# design.net
KiCad netlist of a schematic drawn in Altium Designer
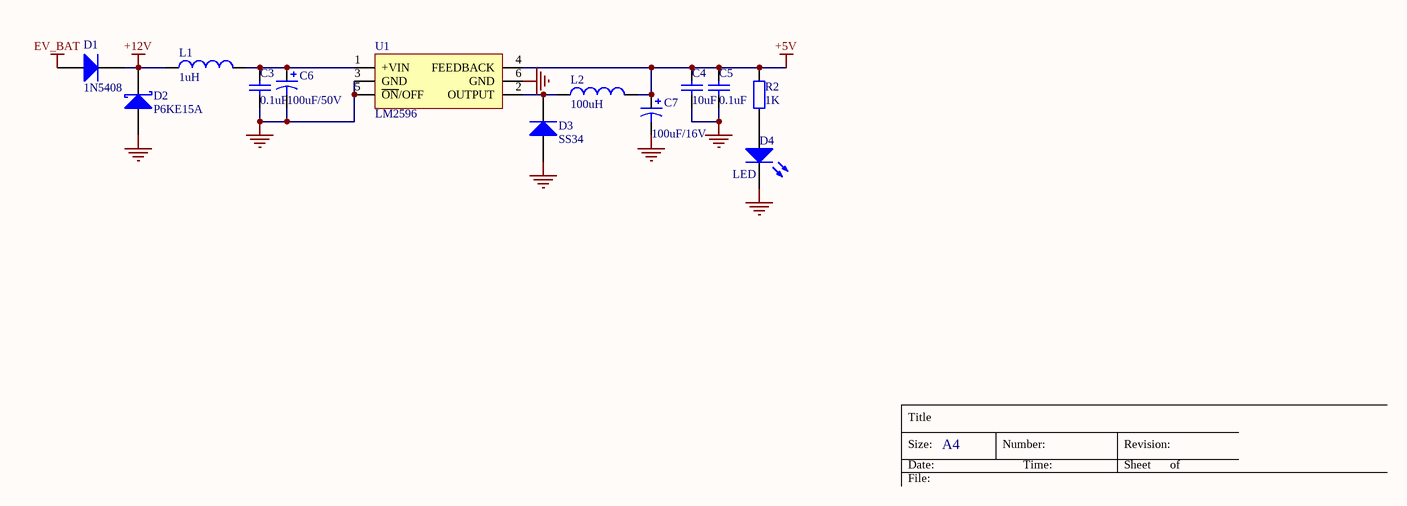
[diagram p0: 电源模块.SchDoc]

(export (version "E")
  (design (tool "Eeschema 10.0.6"))
  (components
    (comp (ref "C3")
      (value "0.1uF")
      (footprint "0603-L")
      (description "Ceramic, X7R, 100V, 10%, 0603")
      (fields (field (name "Comment") "Cap") (field (name "PUBLISHER") "Altium Limited"))
      (libsource (lib "Resistor") (part "CC0603KRX7R0BB104"))
    )
    (comp (ref "C4")
      (value "10uF")
      (footprint "0603-L")
      (description "Capacitor")
      (fields (field (name "Comment") "Cap") (field (name "PUBLISHER") "Altium Limited"))
      (libsource (lib "Miscellaneous Devices") (part "Cap"))
    )
    (comp (ref "C5")
      (value "0.1uF")
      (footprint "0603-L")
      (description "Ceramic, X7R, 100V, 10%, 0603")
      (fields (field (name "Comment") "Cap") (field (name "PUBLISHER") "Altium Limited"))
      (libsource (lib "Resistor") (part "CC0603KRX7R0BB104"))
    )
    (comp (ref "C6")
      (value "100uF/50V")
      (footprint "CAP220uF,16V,6.3*7.7mm")
      (description "Polarized Capacitor (Radial)")
      (fields (field (name "Comment") "Cap Pol1") (field (name "PUBLISHER") "Altium Limited"))
      (libsource (lib "Miscellaneous Devices") (part "Cap Pol1"))
    )
    (comp (ref "C7")
      (value "100uF/16V")
      (footprint "CAP220uF,16V,6.3*7.7mm")
      (description "Polarized Capacitor (Radial)")
      (fields (field (name "Comment") "Cap Pol1") (field (name "PUBLISHER") "Altium Limited"))
      (libsource (lib "Miscellaneous Devices") (part "Cap Pol1"))
    )
    (comp (ref "D1")
      (value "1N5408")
      (footprint "DO-201AD")
      (description "3 Amp Medium Power Silicon Rectifier Diode")
      (fields (field (name "PUBLISHER") "Altium Limited"))
      (libsource (lib "Miscellaneous Devices") (part "Diode 1N5408"))
    )
    (comp (ref "D2")
      (value "P6KE15A")
      (footprint "P6KE15A")
      (description "Schottky Diode")
      (fields (field (name "PUBLISHER") "Altium Limited"))
      (libsource (lib "Miscellaneous Devices") (part "D Schottky"))
    )
    (comp (ref "D3")
      (value "SS34")
      (footprint "SMC")
      (description "3 Amp Medium Power Silicon Rectifier Diode")
      (fields (field (name "PUBLISHER") "Altium Limited"))
      (libsource (lib "Miscellaneous Devices") (part "Diode 1N5408"))
    )
    (comp (ref "D4")
      (value "LED")
      (footprint "0603-L")
      (description "Typical INFRARED GaAs LED")
      (fields (field (name "PUBLISHER") "Altium Limited"))
      (libsource (lib "Miscellaneous Devices") (part "LED0"))
    )
    (comp (ref "L1")
      (value "1uH")
      (footprint "0603-L")
      (description "Inductor")
      (fields (field (name "PUBLISHER") "Altium Limited"))
      (libsource (lib "Miscellaneous Devices") (part "Inductor"))
    )
    (comp (ref "L2")
      (value "100uH")
      (footprint "IND-10*10*5")
      (description "Inductor")
      (fields (field (name "PUBLISHER") "Altium Limited"))
      (libsource (lib "Miscellaneous Devices") (part "Inductor"))
    )
    (comp (ref "R2")
      (value "1K")
      (footprint "0603-L")
      (description "Resistor")
      (fields (field (name "Comment") "Res2") (field (name "PUBLISHER") "Altium Limited"))
      (libsource (lib "Miscellaneous Devices") (part "Res2"))
    )
    (comp (ref "U1") (value "LM2596") (footprint "TO263, LM2576") (libsource (lib "BMS") (part "LM2576")))
  )
  (nets
    (net (code "1") (name "+5V") (class "Default")
      (node (ref "C4") (pin "2") (pinfunction "2_2") (pintype "passive"))
      (node (ref "C5") (pin "2") (pinfunction "2_2") (pintype "passive"))
      (node (ref "C7") (pin "1") (pinfunction "1_1") (pintype "passive"))
      (node (ref "L2") (pin "2") (pinfunction "2_2") (pintype "passive"))
      (node (ref "R2") (pin "1") (pinfunction "1_1") (pintype "passive"))
      (node (ref "U1") (pin "4") (pinfunction "FEEDBACK_4") (pintype "power_in"))
    )
    (net (code "2") (name "+12V") (class "Default")
      (node (ref "D1") (pin "2") (pinfunction "K_2") (pintype "passive"))
      (node (ref "D2") (pin "2") (pinfunction "K_2") (pintype "passive"))
      (node (ref "L1") (pin "1") (pinfunction "1_1") (pintype "passive"))
    )
    (net (code "3") (name "EV_BAT") (class "Default")
      (node (ref "D1") (pin "1") (pinfunction "A_1") (pintype "passive"))
    )
    (net (code "4") (name "GND") (class "Default")
      (node (ref "C3") (pin "1") (pinfunction "1_1") (pintype "passive"))
      (node (ref "C4") (pin "1") (pinfunction "1_1") (pintype "passive"))
      (node (ref "C5") (pin "1") (pinfunction "1_1") (pintype "passive"))
      (node (ref "C6") (pin "2") (pinfunction "2_2") (pintype "passive"))
      (node (ref "C7") (pin "2") (pinfunction "2_2") (pintype "passive"))
      (node (ref "D2") (pin "1") (pinfunction "A_1") (pintype "passive"))
      (node (ref "D3") (pin "1") (pinfunction "A_1") (pintype "passive"))
      (node (ref "D4") (pin "2") (pinfunction "K_2") (pintype "passive"))
      (node (ref "U1") (pin "3") (pinfunction "GND_3") (pintype "power_in"))
      (node (ref "U1") (pin "5") (pinfunction "~{ON}/OFF_5") (pintype "power_in"))
      (node (ref "U1") (pin "6") (pinfunction "GND_6") (pintype "power_in"))
    )
    (net (code "5") (name "Net-(D3-K)") (class "Default")
      (node (ref "D3") (pin "2") (pinfunction "K_2") (pintype "passive"))
      (node (ref "L2") (pin "1") (pinfunction "1_1") (pintype "passive"))
      (node (ref "U1") (pin "2") (pinfunction "OUTPUT_2") (pintype "power_in"))
    )
    (net (code "6") (name "Net-(D4-A)") (class "Default")
      (node (ref "D4") (pin "1") (pinfunction "A_1") (pintype "passive"))
      (node (ref "R2") (pin "2") (pinfunction "2_2") (pintype "passive"))
    )
    (net (code "7") (name "Net-(U1-+VIN)") (class "Default")
      (node (ref "C3") (pin "2") (pinfunction "2_2") (pintype "passive"))
      (node (ref "C6") (pin "1") (pinfunction "1_1") (pintype "passive"))
      (node (ref "L1") (pin "2") (pinfunction "2_2") (pintype "passive"))
      (node (ref "U1") (pin "1") (pinfunction "+VIN_1") (pintype "power_in"))
    )
  )
)
